# Esquema.net
KiCad netlist of a schematic drawn in EAGLE
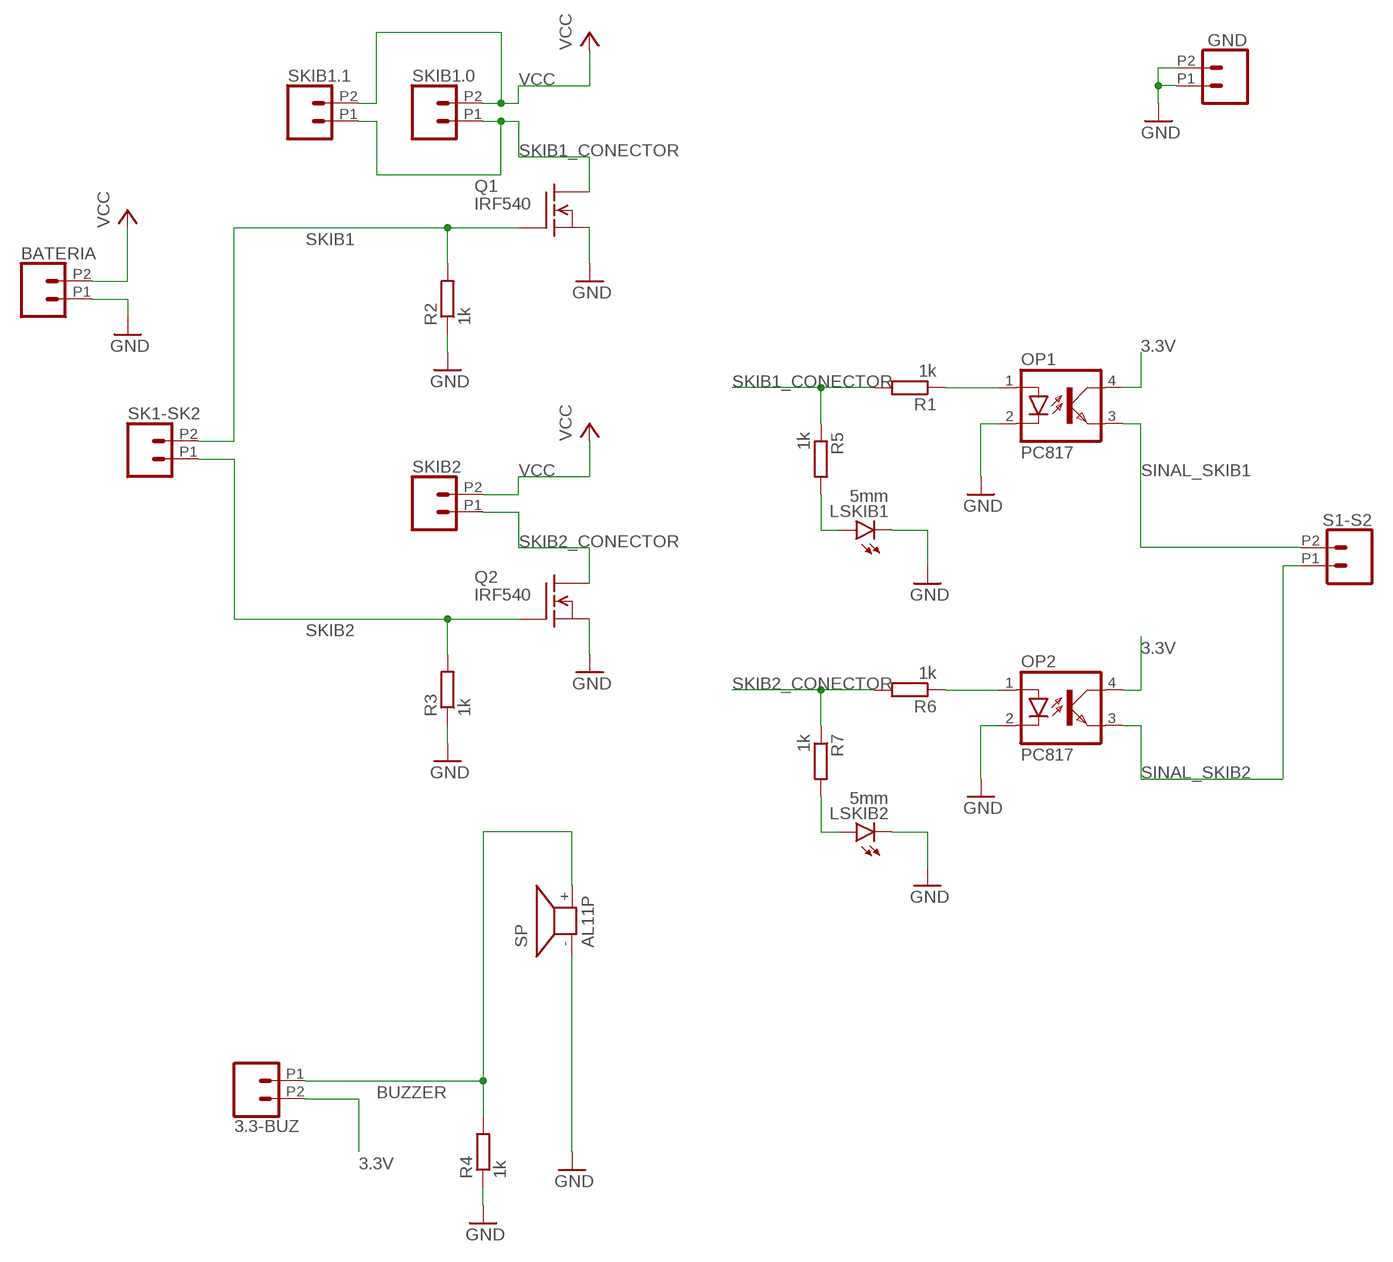
[diagram p0: schematic, sheet 1]

(export (version "E")
  (design (tool "Eeschema 10.0.6"))
  (components
    (comp (ref "3.3-BUZ")
      (value "CONN_022.54MM_SCREWTERM")
      (footprint "eagle-import:1X02_2.54_SCREWTERM")
      (libsource (lib "eagle-import") (part "CONN_022.54MM_SCREWTERM"))
    )
    (comp (ref "BATERIA")
      (value "CONN_022.54MM_SCREWTERM")
      (footprint "eagle-import:1X02_2.54_SCREWTERM")
      (libsource (lib "eagle-import") (part "CONN_022.54MM_SCREWTERM"))
    )
    (comp (ref "GND")
      (value "CONN_022.54MM_SCREWTERM")
      (footprint "eagle-import:1X02_2.54_SCREWTERM")
      (libsource (lib "eagle-import") (part "CONN_022.54MM_SCREWTERM"))
    )
    (comp (ref "LSKIB1")
      (value "5mm")
      (footprint "eagle-import:LED5MM")
      (libsource (lib "eagle-import") (part "LED5MM"))
    )
    (comp (ref "LSKIB2")
      (value "5mm")
      (footprint "eagle-import:LED5MM")
      (libsource (lib "eagle-import") (part "LED5MM"))
    )
    (comp (ref "OP1")
      (value "PC817")
      (footprint "eagle-import:DIL04")
      (fields (field (name "MPN") "PC817X4J000F"))
      (libsource (lib "eagle-import") (part "PC817"))
    )
    (comp (ref "OP2")
      (value "PC817")
      (footprint "eagle-import:DIL04")
      (fields (field (name "MPN") "PC817X4J000F"))
      (libsource (lib "eagle-import") (part "PC817"))
    )
    (comp (ref "Q1")
      (value "IRF540")
      (footprint "eagle-import:TO220")
      (libsource (lib "eagle-import") (part "IRF540"))
    )
    (comp (ref "Q2")
      (value "IRF540")
      (footprint "eagle-import:TO220")
      (libsource (lib "eagle-import") (part "IRF540"))
    )
    (comp (ref "R1")
      (value "1k")
      (footprint "eagle-import:0207_10")
      (libsource (lib "eagle-import") (part "R-EU_0207/10"))
    )
    (comp (ref "R2")
      (value "1k")
      (footprint "eagle-import:0207_10")
      (libsource (lib "eagle-import") (part "R-EU_0207/10"))
    )
    (comp (ref "R3")
      (value "1k")
      (footprint "eagle-import:0207_10")
      (libsource (lib "eagle-import") (part "R-EU_0207/10"))
    )
    (comp (ref "R4")
      (value "1k")
      (footprint "eagle-import:0207_10")
      (libsource (lib "eagle-import") (part "R-EU_0207/10"))
    )
    (comp (ref "R5")
      (value "1k")
      (footprint "eagle-import:0207_10")
      (libsource (lib "eagle-import") (part "R-EU_0207/10"))
    )
    (comp (ref "R6")
      (value "1k")
      (footprint "eagle-import:0207_10")
      (libsource (lib "eagle-import") (part "R-EU_0207/10"))
    )
    (comp (ref "R7")
      (value "1k")
      (footprint "eagle-import:0207_10")
      (libsource (lib "eagle-import") (part "R-EU_0207/10"))
    )
    (comp (ref "S1-S2")
      (value "CONN_022.54MM_SCREWTERM")
      (footprint "eagle-import:1X02_2.54_SCREWTERM")
      (libsource (lib "eagle-import") (part "CONN_022.54MM_SCREWTERM"))
    )
    (comp (ref "SK1-SK2")
      (value "CONN_022.54MM_SCREWTERM")
      (footprint "eagle-import:1X02_2.54_SCREWTERM")
      (libsource (lib "eagle-import") (part "CONN_022.54MM_SCREWTERM"))
    )
    (comp (ref "SKIB1.0")
      (value "CONN_022.54MM_SCREWTERM")
      (footprint "eagle-import:1X02_2.54_SCREWTERM")
      (libsource (lib "eagle-import") (part "CONN_022.54MM_SCREWTERM"))
    )
    (comp (ref "SKIB1.1")
      (value "CONN_022.54MM_SCREWTERM")
      (footprint "eagle-import:1X02_2.54_SCREWTERM")
      (libsource (lib "eagle-import") (part "CONN_022.54MM_SCREWTERM"))
    )
    (comp (ref "SKIB2")
      (value "CONN_022.54MM_SCREWTERM")
      (footprint "eagle-import:1X02_2.54_SCREWTERM")
      (libsource (lib "eagle-import") (part "CONN_022.54MM_SCREWTERM"))
    )
    (comp (ref "SP")
      (value "AL11P")
      (footprint "eagle-import:AL11P")
      (libsource (lib "eagle-import") (part "AL11P"))
    )
  )
  (nets
    (net (code "1") (name "/3.3V") (class "Default")
      (node (ref "3.3-BUZ") (pin "P2") (pinfunction "2_P2") (pintype "passive"))
      (node (ref "OP1") (pin "4") (pinfunction "COL_4") (pintype "passive"))
      (node (ref "OP2") (pin "4") (pinfunction "COL_4") (pintype "passive"))
    )
    (net (code "2") (name "/BUZZER") (class "Default")
      (node (ref "3.3-BUZ") (pin "P1") (pinfunction "1_P1") (pintype "passive"))
      (node (ref "R4") (pin "2") (pinfunction "2_2") (pintype "passive"))
      (node (ref "SP") (pin "+") (pinfunction "2_+") (pintype "passive"))
    )
    (net (code "3") (name "/SINAL_SKIB1") (class "Default")
      (node (ref "OP1") (pin "3") (pinfunction "EMIT_3") (pintype "passive"))
      (node (ref "S1-S2") (pin "P2") (pinfunction "2_P2") (pintype "passive"))
    )
    (net (code "4") (name "/SINAL_SKIB2") (class "Default")
      (node (ref "OP2") (pin "3") (pinfunction "EMIT_3") (pintype "passive"))
      (node (ref "S1-S2") (pin "P1") (pinfunction "1_P1") (pintype "passive"))
    )
    (net (code "5") (name "/SKIB1") (class "Default")
      (node (ref "Q1") (pin "1") (pinfunction "G_1") (pintype "passive"))
      (node (ref "R2") (pin "2") (pinfunction "2_2") (pintype "passive"))
      (node (ref "SK1-SK2") (pin "P2") (pinfunction "2_P2") (pintype "passive"))
    )
    (net (code "6") (name "/SKIB1_CONECTOR") (class "Default")
      (node (ref "Q1") (pin "2") (pinfunction "D_2") (pintype "passive"))
      (node (ref "R1") (pin "2") (pinfunction "2_2") (pintype "passive"))
      (node (ref "R5") (pin "1") (pinfunction "1_1") (pintype "passive"))
      (node (ref "SKIB1.0") (pin "P1") (pinfunction "1_P1") (pintype "passive"))
      (node (ref "SKIB1.1") (pin "P1") (pinfunction "1_P1") (pintype "passive"))
    )
    (net (code "7") (name "/SKIB2") (class "Default")
      (node (ref "Q2") (pin "1") (pinfunction "G_1") (pintype "passive"))
      (node (ref "R3") (pin "2") (pinfunction "2_2") (pintype "passive"))
      (node (ref "SK1-SK2") (pin "P1") (pinfunction "1_P1") (pintype "passive"))
    )
    (net (code "8") (name "/SKIB2_CONECTOR") (class "Default")
      (node (ref "Q2") (pin "2") (pinfunction "D_2") (pintype "passive"))
      (node (ref "R6") (pin "2") (pinfunction "2_2") (pintype "passive"))
      (node (ref "R7") (pin "1") (pinfunction "1_1") (pintype "passive"))
      (node (ref "SKIB2") (pin "P1") (pinfunction "1_P1") (pintype "passive"))
    )
    (net (code "9") (name "GND") (class "Default")
      (node (ref "BATERIA") (pin "P1") (pinfunction "1_P1") (pintype "passive"))
      (node (ref "GND") (pin "P1") (pinfunction "1_P1") (pintype "passive"))
      (node (ref "GND") (pin "P2") (pinfunction "2_P2") (pintype "passive"))
      (node (ref "LSKIB1") (pin "K") (pinfunction "C_K") (pintype "passive"))
      (node (ref "LSKIB2") (pin "K") (pinfunction "C_K") (pintype "passive"))
      (node (ref "OP1") (pin "2") (pinfunction "C_2") (pintype "passive"))
      (node (ref "OP2") (pin "2") (pinfunction "C_2") (pintype "passive"))
      (node (ref "Q1") (pin "3") (pinfunction "S_3") (pintype "passive"))
      (node (ref "Q2") (pin "3") (pinfunction "S_3") (pintype "passive"))
      (node (ref "R2") (pin "1") (pinfunction "1_1") (pintype "passive"))
      (node (ref "R3") (pin "1") (pinfunction "1_1") (pintype "passive"))
      (node (ref "R4") (pin "1") (pinfunction "1_1") (pintype "passive"))
      (node (ref "SP") (pin "-") (pinfunction "1_-") (pintype "passive"))
    )
    (net (code "10") (name "Net-(LSKIB1-PadA)") (class "Default")
      (node (ref "LSKIB1") (pin "A") (pinfunction "A_A") (pintype "passive"))
      (node (ref "R5") (pin "2") (pinfunction "2_2") (pintype "passive"))
    )
    (net (code "11") (name "Net-(LSKIB2-PadA)") (class "Default")
      (node (ref "LSKIB2") (pin "A") (pinfunction "A_A") (pintype "passive"))
      (node (ref "R7") (pin "2") (pinfunction "2_2") (pintype "passive"))
    )
    (net (code "12") (name "Net-(OP1-A)") (class "Default")
      (node (ref "OP1") (pin "1") (pinfunction "A_1") (pintype "passive"))
      (node (ref "R1") (pin "1") (pinfunction "1_1") (pintype "passive"))
    )
    (net (code "13") (name "Net-(OP2-A)") (class "Default")
      (node (ref "OP2") (pin "1") (pinfunction "A_1") (pintype "passive"))
      (node (ref "R6") (pin "1") (pinfunction "1_1") (pintype "passive"))
    )
    (net (code "14") (name "VCC") (class "Default")
      (node (ref "BATERIA") (pin "P2") (pinfunction "2_P2") (pintype "passive"))
      (node (ref "SKIB1.0") (pin "P2") (pinfunction "2_P2") (pintype "passive"))
      (node (ref "SKIB1.1") (pin "P2") (pinfunction "2_P2") (pintype "passive"))
      (node (ref "SKIB2") (pin "P2") (pinfunction "2_P2") (pintype "passive"))
    )
  )
)
